# light.net
KiCad netlist of a schematic drawn in EAGLE
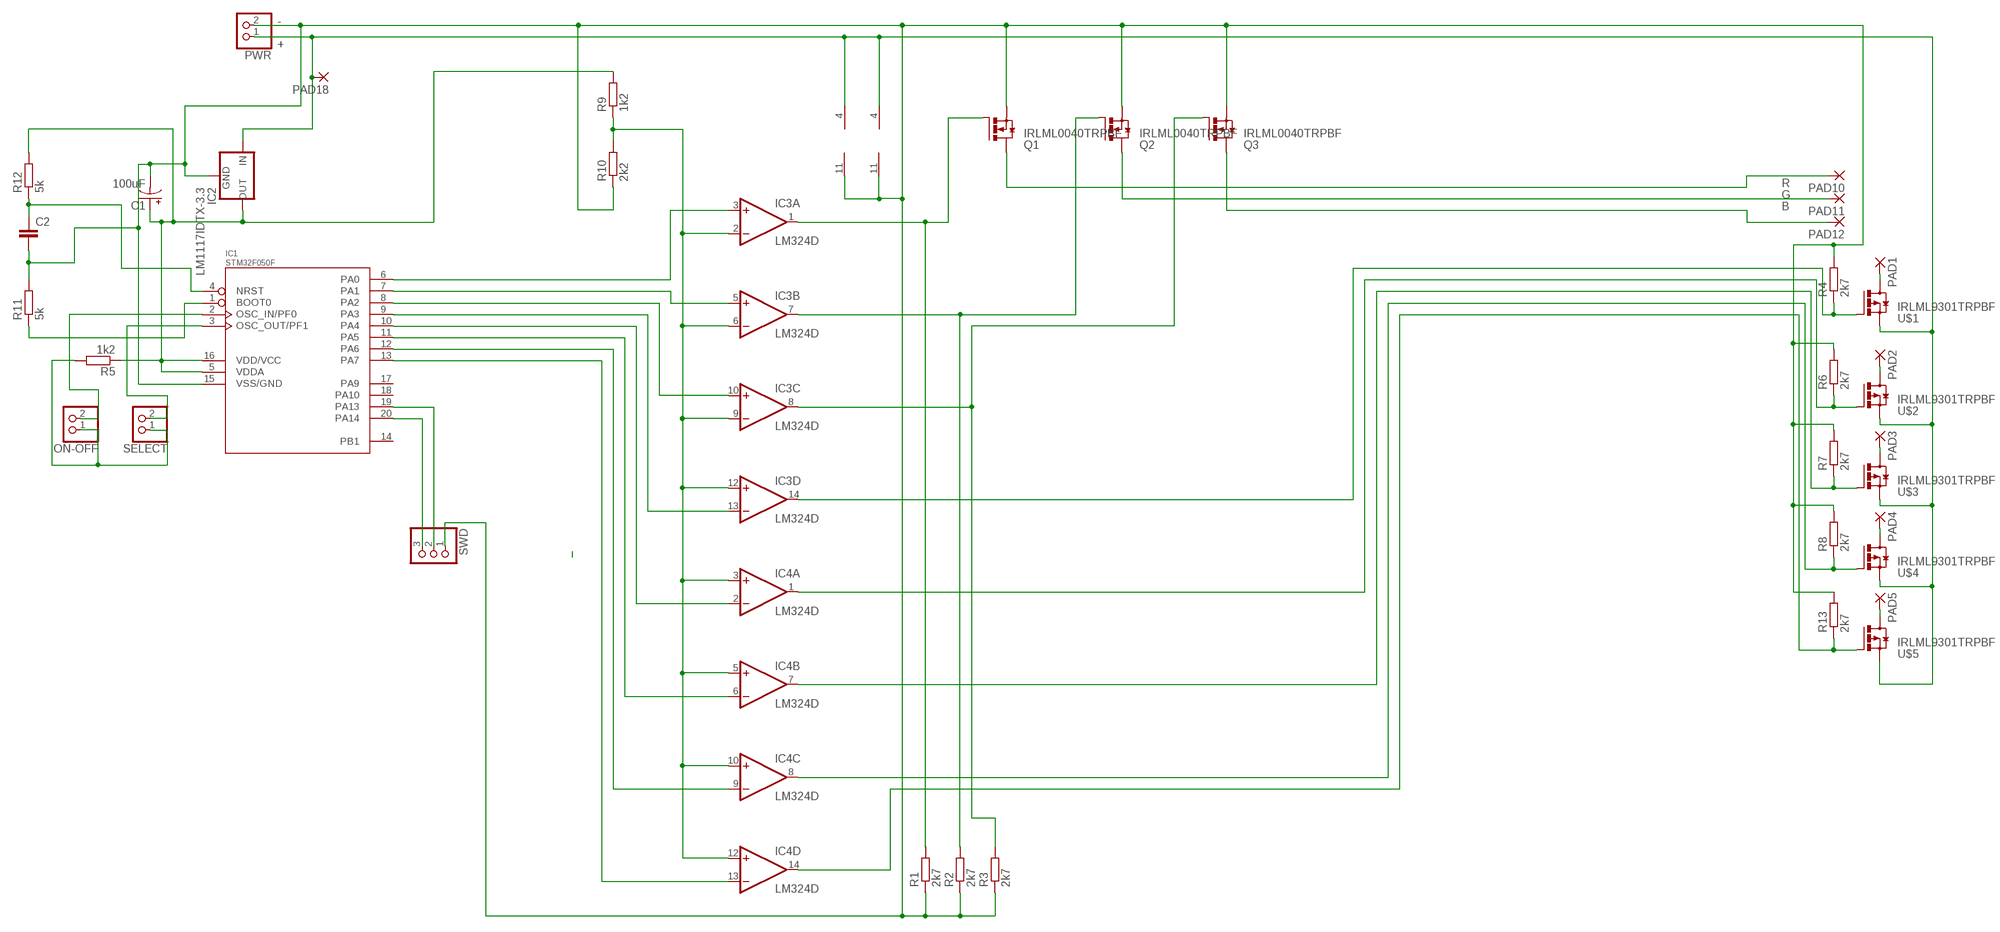
[diagram p0: schematic, sheet 1]

(export (version "E")
  (design (tool "Eeschema 10.0.6"))
  (components
    (comp (ref "C1")
      (value "100uF")
      (footprint "eagle-import:SMC_D")
      (libsource (lib "eagle-import") (part "CPOL-USSMCD"))
    )
    (comp (ref "C2")
      (value "C-EUC1206")
      (footprint "eagle-import:C1206")
      (libsource (lib "eagle-import") (part "C-EUC1206"))
    )
    (comp (ref "IC1")
      (value "STM32F050F")
      (footprint "eagle-import:TSSOP20")
      (libsource (lib "eagle-import") (part "STM32F050F"))
    )
    (comp (ref "IC2")
      (value "LM1117IDTX-3.3")
      (footprint "eagle-import:TO252")
      (libsource (lib "eagle-import") (part "LM1117IDTX-3.3"))
    )
    (comp (ref "IC3")
      (value "LM324D")
      (footprint "eagle-import:SO14")
      (libsource (lib "eagle-import") (part "LM324D"))
    )
    (comp (ref "IC4")
      (value "LM324D")
      (footprint "eagle-import:SO14")
      (libsource (lib "eagle-import") (part "LM324D"))
    )
    (comp (ref "ON-OFF")
      (value "PINHD-1X2")
      (footprint "eagle-import:1X02")
      (libsource (lib "eagle-import") (part "PINHD-1X2"))
    )
    (comp (ref "PAD1")
      (value "SMD2")
      (footprint "eagle-import:SMD1,27-2,54")
      (libsource (lib "eagle-import") (part "SMD2"))
    )
    (comp (ref "PAD2")
      (value "SMD2")
      (footprint "eagle-import:SMD1,27-2,54")
      (libsource (lib "eagle-import") (part "SMD2"))
    )
    (comp (ref "PAD3")
      (value "SMD2")
      (footprint "eagle-import:SMD1,27-2,54")
      (libsource (lib "eagle-import") (part "SMD2"))
    )
    (comp (ref "PAD4")
      (value "SMD2")
      (footprint "eagle-import:SMD1,27-2,54")
      (libsource (lib "eagle-import") (part "SMD2"))
    )
    (comp (ref "PAD5")
      (value "SMD2")
      (footprint "eagle-import:SMD1,27-2,54")
      (libsource (lib "eagle-import") (part "SMD2"))
    )
    (comp (ref "PAD10")
      (value "SMD2")
      (footprint "eagle-import:SMD1,27-2,54")
      (libsource (lib "eagle-import") (part "SMD2"))
    )
    (comp (ref "PAD11")
      (value "SMD2")
      (footprint "eagle-import:SMD1,27-2,54")
      (libsource (lib "eagle-import") (part "SMD2"))
    )
    (comp (ref "PAD12")
      (value "SMD2")
      (footprint "eagle-import:SMD1,27-2,54")
      (libsource (lib "eagle-import") (part "SMD2"))
    )
    (comp (ref "PAD18")
      (value "SMD2")
      (footprint "eagle-import:SMD1,27-2,54")
      (libsource (lib "eagle-import") (part "SMD2"))
    )
    (comp (ref "PWR")
      (value "PINHD-1X2")
      (footprint "eagle-import:1X02")
      (libsource (lib "eagle-import") (part "PINHD-1X2"))
    )
    (comp (ref "Q1")
      (value "IRLML0040TRPBF")
      (footprint "eagle-import:MICRO3")
      (libsource (lib "eagle-import") (part "IRLML0040TRPBF"))
    )
    (comp (ref "Q2")
      (value "IRLML0040TRPBF")
      (footprint "eagle-import:MICRO3")
      (libsource (lib "eagle-import") (part "IRLML0040TRPBF"))
    )
    (comp (ref "Q3")
      (value "IRLML0040TRPBF")
      (footprint "eagle-import:MICRO3")
      (libsource (lib "eagle-import") (part "IRLML0040TRPBF"))
    )
    (comp (ref "R1")
      (value "2k7")
      (footprint "eagle-import:M1206")
      (libsource (lib "eagle-import") (part "R-EU_M1206"))
    )
    (comp (ref "R2")
      (value "2k7")
      (footprint "eagle-import:M1206")
      (libsource (lib "eagle-import") (part "R-EU_M1206"))
    )
    (comp (ref "R3")
      (value "2k7")
      (footprint "eagle-import:M1206")
      (libsource (lib "eagle-import") (part "R-EU_M1206"))
    )
    (comp (ref "R4")
      (value "2k7")
      (footprint "eagle-import:M1206")
      (libsource (lib "eagle-import") (part "R-EU_M1206"))
    )
    (comp (ref "R5")
      (value "1k2")
      (footprint "eagle-import:M1206")
      (libsource (lib "eagle-import") (part "R-EU_M1206"))
    )
    (comp (ref "R6")
      (value "2k7")
      (footprint "eagle-import:M1206")
      (libsource (lib "eagle-import") (part "R-EU_M1206"))
    )
    (comp (ref "R7")
      (value "2k7")
      (footprint "eagle-import:M1206")
      (libsource (lib "eagle-import") (part "R-EU_M1206"))
    )
    (comp (ref "R8")
      (value "2k7")
      (footprint "eagle-import:M1206")
      (libsource (lib "eagle-import") (part "R-EU_M1206"))
    )
    (comp (ref "R9")
      (value "1k2")
      (footprint "eagle-import:M1206")
      (libsource (lib "eagle-import") (part "R-EU_M1206"))
    )
    (comp (ref "R10")
      (value "2k2")
      (footprint "eagle-import:M1206")
      (libsource (lib "eagle-import") (part "R-EU_M1206"))
    )
    (comp (ref "R11")
      (value "5k")
      (footprint "eagle-import:M1206")
      (libsource (lib "eagle-import") (part "R-EU_M1206"))
    )
    (comp (ref "R12")
      (value "5k")
      (footprint "eagle-import:M1206")
      (libsource (lib "eagle-import") (part "R-EU_M1206"))
    )
    (comp (ref "R13")
      (value "2k7")
      (footprint "eagle-import:M1206")
      (libsource (lib "eagle-import") (part "R-EU_M1206"))
    )
    (comp (ref "SELECT")
      (value "PINHD-1X2")
      (footprint "eagle-import:1X02")
      (libsource (lib "eagle-import") (part "PINHD-1X2"))
    )
    (comp (ref "SWD")
      (value "PINHD-1X3")
      (footprint "eagle-import:1X03")
      (libsource (lib "eagle-import") (part "PINHD-1X3"))
    )
    (comp (ref "U$1")
      (value "IRLML9301TRPBF")
      (footprint "eagle-import:MICRO3")
      (libsource (lib "eagle-import") (part "IRLML9301TRPBF"))
    )
    (comp (ref "U$2")
      (value "IRLML9301TRPBF")
      (footprint "eagle-import:MICRO3")
      (libsource (lib "eagle-import") (part "IRLML9301TRPBF"))
    )
    (comp (ref "U$3")
      (value "IRLML9301TRPBF")
      (footprint "eagle-import:MICRO3")
      (libsource (lib "eagle-import") (part "IRLML9301TRPBF"))
    )
    (comp (ref "U$4")
      (value "IRLML9301TRPBF")
      (footprint "eagle-import:MICRO3")
      (libsource (lib "eagle-import") (part "IRLML9301TRPBF"))
    )
    (comp (ref "U$5")
      (value "IRLML9301TRPBF")
      (footprint "eagle-import:MICRO3")
      (libsource (lib "eagle-import") (part "IRLML9301TRPBF"))
    )
  )
  (nets
    (net (code "1") (name "Net-(IC1-BOOT0)") (class "Default")
      (node (ref "IC1") (pin "1") (pinfunction "BOOT0_1") (pintype "bidirectional"))
      (node (ref "R11") (pin "1") (pinfunction "1_1") (pintype "passive"))
    )
    (net (code "2") (name "Net-(IC1-NRST)") (class "Default")
      (node (ref "C2") (pin "1") (pinfunction "1_1") (pintype "passive"))
      (node (ref "IC1") (pin "4") (pinfunction "NRST_4") (pintype "bidirectional"))
      (node (ref "R12") (pin "1") (pinfunction "1_1") (pintype "passive"))
    )
    (net (code "3") (name "Net-(IC1-OSC_IN{slash}PF0)") (class "Default")
      (node (ref "IC1") (pin "2") (pinfunction "OSC_IN/PF0_2") (pintype "bidirectional"))
      (node (ref "ON-OFF") (pin "2") (pinfunction "2_2") (pintype "passive"))
    )
    (net (code "4") (name "Net-(IC1-OSC_OUT{slash}PF1)") (class "Default")
      (node (ref "IC1") (pin "3") (pinfunction "OSC_OUT/PF1_3") (pintype "bidirectional"))
      (node (ref "SELECT") (pin "2") (pinfunction "2_2") (pintype "passive"))
    )
    (net (code "5") (name "Net-(IC1-PA0)") (class "Default")
      (node (ref "IC1") (pin "6") (pinfunction "PA0_6") (pintype "bidirectional"))
      (node (ref "IC3") (pin "3") (pinfunction "+IN_3") (pintype "input"))
    )
    (net (code "6") (name "Net-(IC1-PA1)") (class "Default")
      (node (ref "IC1") (pin "7") (pinfunction "PA1_7") (pintype "bidirectional"))
      (node (ref "IC3") (pin "5") (pinfunction "+IN_5") (pintype "input"))
    )
    (net (code "7") (name "Net-(IC1-PA2)") (class "Default")
      (node (ref "IC1") (pin "8") (pinfunction "PA2_8") (pintype "bidirectional"))
      (node (ref "IC3") (pin "10") (pinfunction "+IN_10") (pintype "input"))
    )
    (net (code "8") (name "Net-(IC1-PA3)") (class "Default")
      (node (ref "IC1") (pin "9") (pinfunction "PA3_9") (pintype "bidirectional"))
      (node (ref "IC3") (pin "13") (pinfunction "-IN_13") (pintype "input"))
    )
    (net (code "9") (name "Net-(IC1-PA4)") (class "Default")
      (node (ref "IC1") (pin "10") (pinfunction "PA4_10") (pintype "bidirectional"))
      (node (ref "IC4") (pin "2") (pinfunction "-IN_2") (pintype "input"))
    )
    (net (code "10") (name "Net-(IC1-PA5)") (class "Default")
      (node (ref "IC1") (pin "11") (pinfunction "PA5_11") (pintype "bidirectional"))
      (node (ref "IC4") (pin "6") (pinfunction "-IN_6") (pintype "input"))
    )
    (net (code "11") (name "Net-(IC1-PA6)") (class "Default")
      (node (ref "IC1") (pin "12") (pinfunction "PA6_12") (pintype "bidirectional"))
      (node (ref "IC4") (pin "9") (pinfunction "-IN_9") (pintype "input"))
    )
    (net (code "12") (name "Net-(IC1-PA7)") (class "Default")
      (node (ref "IC1") (pin "13") (pinfunction "PA7_13") (pintype "bidirectional"))
      (node (ref "IC4") (pin "13") (pinfunction "-IN_13") (pintype "input"))
    )
    (net (code "13") (name "Net-(IC1-PA13)") (class "Default")
      (node (ref "IC1") (pin "19") (pinfunction "PA13_19") (pintype "bidirectional"))
      (node (ref "SWD") (pin "2") (pinfunction "2_2") (pintype "passive"))
    )
    (net (code "14") (name "Net-(IC1-PA14)") (class "Default")
      (node (ref "IC1") (pin "20") (pinfunction "PA14_20") (pintype "bidirectional"))
      (node (ref "SWD") (pin "3") (pinfunction "3_3") (pintype "passive"))
    )
    (net (code "15") (name "Net-(IC1-VDDA)") (class "Default")
      (node (ref "C1") (pin "+") (pinfunction "+_+") (pintype "passive"))
      (node (ref "IC1") (pin "16") (pinfunction "VDD/VCC_16") (pintype "power_in"))
      (node (ref "IC1") (pin "5") (pinfunction "VDDA_5") (pintype "power_in"))
      (node (ref "IC2") (pin "TAB") (pinfunction "OUT_TAB") (pintype "passive"))
      (node (ref "R12") (pin "2") (pinfunction "2_2") (pintype "passive"))
      (node (ref "R5") (pin "1") (pinfunction "1_1") (pintype "passive"))
      (node (ref "R9") (pin "2") (pinfunction "2_2") (pintype "passive"))
    )
    (net (code "16") (name "Net-(IC1-VSS{slash}GND)") (class "Default")
      (node (ref "C1") (pin "-") (pinfunction "-_-") (pintype "passive"))
      (node (ref "C2") (pin "2") (pinfunction "2_2") (pintype "passive"))
      (node (ref "IC1") (pin "15") (pinfunction "VSS/GND_15") (pintype "power_in"))
      (node (ref "IC2") (pin "1") (pinfunction "GND_1") (pintype "input"))
      (node (ref "IC3") (pin "11") (pinfunction "V-_11") (pintype "power_in"))
      (node (ref "IC4") (pin "11") (pinfunction "V-_11") (pintype "power_in"))
      (node (ref "PWR") (pin "2") (pinfunction "2_2") (pintype "passive"))
      (node (ref "Q1") (pin "2") (pinfunction "S_2") (pintype "passive"))
      (node (ref "Q2") (pin "2") (pinfunction "S_2") (pintype "passive"))
      (node (ref "Q3") (pin "2") (pinfunction "S_2") (pintype "passive"))
      (node (ref "R1") (pin "1") (pinfunction "1_1") (pintype "passive"))
      (node (ref "R10") (pin "1") (pinfunction "1_1") (pintype "passive"))
      (node (ref "R11") (pin "2") (pinfunction "2_2") (pintype "passive"))
      (node (ref "R13") (pin "2") (pinfunction "2_2") (pintype "passive"))
      (node (ref "R2") (pin "1") (pinfunction "1_1") (pintype "passive"))
      (node (ref "R3") (pin "1") (pinfunction "1_1") (pintype "passive"))
      (node (ref "R4") (pin "2") (pinfunction "2_2") (pintype "passive"))
      (node (ref "R6") (pin "2") (pinfunction "2_2") (pintype "passive"))
      (node (ref "R7") (pin "2") (pinfunction "2_2") (pintype "passive"))
      (node (ref "R8") (pin "2") (pinfunction "2_2") (pintype "passive"))
      (node (ref "SWD") (pin "1") (pinfunction "1_1") (pintype "passive"))
    )
    (net (code "17") (name "Net-(IC2-IN)") (class "Default")
      (node (ref "IC2") (pin "2") (pinfunction "IN_2") (pintype "input"))
      (node (ref "IC3") (pin "4") (pinfunction "V+_4") (pintype "power_in"))
      (node (ref "IC4") (pin "4") (pinfunction "V+_4") (pintype "power_in"))
      (node (ref "PAD18") (pin "1") (pinfunction "P_1") (pintype "passive"))
      (node (ref "PWR") (pin "1") (pinfunction "1_1") (pintype "passive"))
      (node (ref "U$1") (pin "2") (pinfunction "S_2") (pintype "passive"))
      (node (ref "U$2") (pin "2") (pinfunction "S_2") (pintype "passive"))
      (node (ref "U$3") (pin "2") (pinfunction "S_2") (pintype "passive"))
      (node (ref "U$4") (pin "2") (pinfunction "S_2") (pintype "passive"))
      (node (ref "U$5") (pin "2") (pinfunction "S_2") (pintype "passive"))
    )
    (net (code "18") (name "Net-(IC3A--IN)") (class "Default")
      (node (ref "IC3") (pin "12") (pinfunction "+IN_12") (pintype "input"))
      (node (ref "IC3") (pin "2") (pinfunction "-IN_2") (pintype "input"))
      (node (ref "IC3") (pin "6") (pinfunction "-IN_6") (pintype "input"))
      (node (ref "IC3") (pin "9") (pinfunction "-IN_9") (pintype "input"))
      (node (ref "IC4") (pin "10") (pinfunction "+IN_10") (pintype "input"))
      (node (ref "IC4") (pin "12") (pinfunction "+IN_12") (pintype "input"))
      (node (ref "IC4") (pin "3") (pinfunction "+IN_3") (pintype "input"))
      (node (ref "IC4") (pin "5") (pinfunction "+IN_5") (pintype "input"))
      (node (ref "R10") (pin "2") (pinfunction "2_2") (pintype "passive"))
      (node (ref "R9") (pin "1") (pinfunction "1_1") (pintype "passive"))
    )
    (net (code "19") (name "Net-(IC3A-OUT)") (class "Default")
      (node (ref "IC3") (pin "1") (pinfunction "OUT_1") (pintype "output"))
      (node (ref "Q1") (pin "1") (pinfunction "G_1") (pintype "passive"))
      (node (ref "R1") (pin "2") (pinfunction "2_2") (pintype "passive"))
    )
    (net (code "20") (name "Net-(IC3B-OUT)") (class "Default")
      (node (ref "IC3") (pin "7") (pinfunction "OUT_7") (pintype "output"))
      (node (ref "Q2") (pin "1") (pinfunction "G_1") (pintype "passive"))
      (node (ref "R2") (pin "2") (pinfunction "2_2") (pintype "passive"))
    )
    (net (code "21") (name "Net-(IC3C-OUT)") (class "Default")
      (node (ref "IC3") (pin "8") (pinfunction "OUT_8") (pintype "output"))
      (node (ref "Q3") (pin "1") (pinfunction "G_1") (pintype "passive"))
      (node (ref "R3") (pin "2") (pinfunction "2_2") (pintype "passive"))
    )
    (net (code "22") (name "Net-(IC3D-OUT)") (class "Default")
      (node (ref "IC3") (pin "14") (pinfunction "OUT_14") (pintype "output"))
      (node (ref "R4") (pin "1") (pinfunction "1_1") (pintype "passive"))
      (node (ref "U$1") (pin "1") (pinfunction "G_1") (pintype "passive"))
    )
    (net (code "23") (name "Net-(IC4A-OUT)") (class "Default")
      (node (ref "IC4") (pin "1") (pinfunction "OUT_1") (pintype "output"))
      (node (ref "R6") (pin "1") (pinfunction "1_1") (pintype "passive"))
      (node (ref "U$2") (pin "1") (pinfunction "G_1") (pintype "passive"))
    )
    (net (code "24") (name "Net-(IC4B-OUT)") (class "Default")
      (node (ref "IC4") (pin "7") (pinfunction "OUT_7") (pintype "output"))
      (node (ref "R7") (pin "1") (pinfunction "1_1") (pintype "passive"))
      (node (ref "U$3") (pin "1") (pinfunction "G_1") (pintype "passive"))
    )
    (net (code "25") (name "Net-(IC4C-OUT)") (class "Default")
      (node (ref "IC4") (pin "8") (pinfunction "OUT_8") (pintype "output"))
      (node (ref "R8") (pin "1") (pinfunction "1_1") (pintype "passive"))
      (node (ref "U$4") (pin "1") (pinfunction "G_1") (pintype "passive"))
    )
    (net (code "26") (name "Net-(IC4D-OUT)") (class "Default")
      (node (ref "IC4") (pin "14") (pinfunction "OUT_14") (pintype "output"))
      (node (ref "R13") (pin "1") (pinfunction "1_1") (pintype "passive"))
      (node (ref "U$5") (pin "1") (pinfunction "G_1") (pintype "passive"))
    )
    (net (code "27") (name "Net-(ON-OFF-Pad1)") (class "Default")
      (node (ref "ON-OFF") (pin "1") (pinfunction "1_1") (pintype "passive"))
      (node (ref "R5") (pin "2") (pinfunction "2_2") (pintype "passive"))
      (node (ref "SELECT") (pin "1") (pinfunction "1_1") (pintype "passive"))
    )
    (net (code "28") (name "Net-(PAD1-P)") (class "Default")
      (node (ref "PAD1") (pin "1") (pinfunction "P_1") (pintype "passive"))
      (node (ref "U$1") (pin "3") (pinfunction "D_3") (pintype "passive"))
    )
    (net (code "29") (name "Net-(PAD2-P)") (class "Default")
      (node (ref "PAD2") (pin "1") (pinfunction "P_1") (pintype "passive"))
      (node (ref "U$2") (pin "3") (pinfunction "D_3") (pintype "passive"))
    )
    (net (code "30") (name "Net-(PAD3-P)") (class "Default")
      (node (ref "PAD3") (pin "1") (pinfunction "P_1") (pintype "passive"))
      (node (ref "U$3") (pin "3") (pinfunction "D_3") (pintype "passive"))
    )
    (net (code "31") (name "Net-(PAD4-P)") (class "Default")
      (node (ref "PAD4") (pin "1") (pinfunction "P_1") (pintype "passive"))
      (node (ref "U$4") (pin "3") (pinfunction "D_3") (pintype "passive"))
    )
    (net (code "32") (name "Net-(PAD5-P)") (class "Default")
      (node (ref "PAD5") (pin "1") (pinfunction "P_1") (pintype "passive"))
      (node (ref "U$5") (pin "3") (pinfunction "D_3") (pintype "passive"))
    )
    (net (code "33") (name "Net-(PAD10-P)") (class "Default")
      (node (ref "PAD10") (pin "1") (pinfunction "P_1") (pintype "passive"))
      (node (ref "Q1") (pin "3") (pinfunction "D_3") (pintype "passive"))
    )
    (net (code "34") (name "Net-(PAD11-P)") (class "Default")
      (node (ref "PAD11") (pin "1") (pinfunction "P_1") (pintype "passive"))
      (node (ref "Q2") (pin "3") (pinfunction "D_3") (pintype "passive"))
    )
    (net (code "35") (name "Net-(PAD12-P)") (class "Default")
      (node (ref "PAD12") (pin "1") (pinfunction "P_1") (pintype "passive"))
      (node (ref "Q3") (pin "3") (pinfunction "D_3") (pintype "passive"))
    )
    (net (code "36") (name "unconnected-(IC1-PA9-Pad17)") (class "Default")
      (node (ref "IC1") (pin "17") (pinfunction "PA9_17") (pintype "bidirectional"))
    )
    (net (code "37") (name "unconnected-(IC1-PA10-Pad18)") (class "Default")
      (node (ref "IC1") (pin "18") (pinfunction "PA10_18") (pintype "bidirectional"))
    )
    (net (code "38") (name "unconnected-(IC1-PB1-Pad14)") (class "Default")
      (node (ref "IC1") (pin "14") (pinfunction "PB1_14") (pintype "bidirectional"))
    )
  )
)
